# Mirrors_Controls.net
KiCad netlist of a schematic drawn in EAGLE
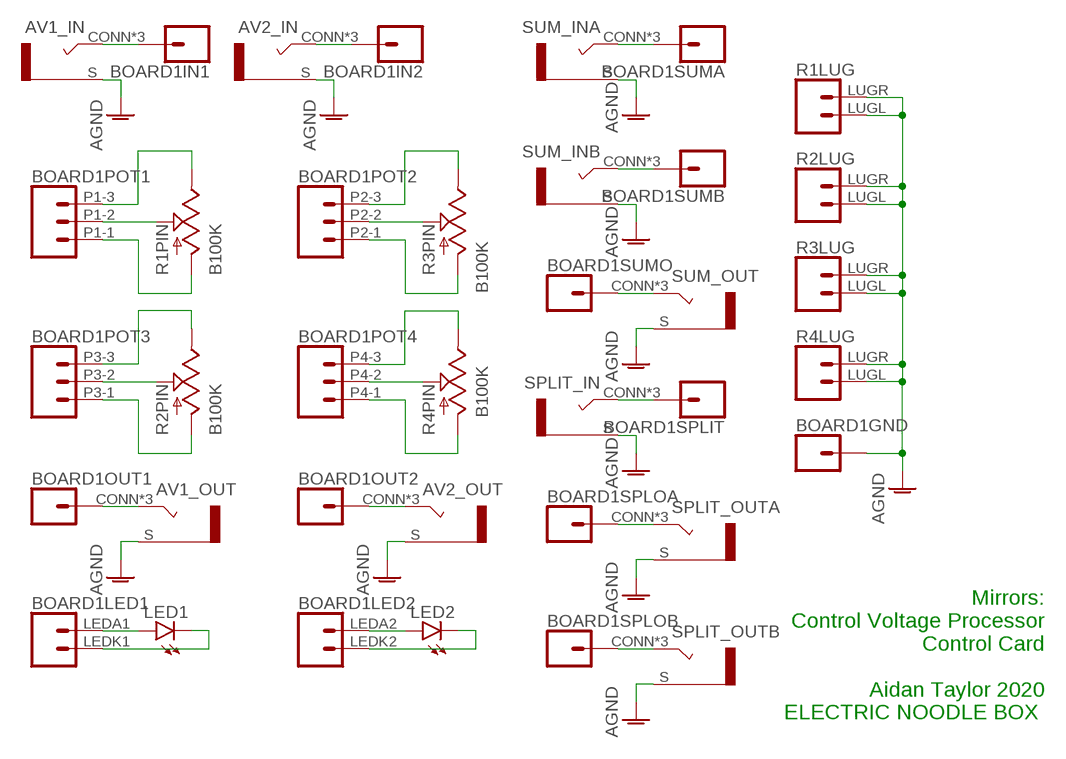
[diagram p0: schematic, sheet 1]

(export (version "E")
  (design (tool "Eeschema 10.0.6"))
  (components
    (comp (ref "AV1_IN")
      (value "COMBI-JACKCINCHNANA")
      (footprint "eagle-import:NEWCOMBOJACK_PANEL")
      (libsource (lib "eagle-import") (part "COMBI-JACKCINCHNANA"))
    )
    (comp (ref "AV1_OUT")
      (value "COMBI-JACKCINCHNANA")
      (footprint "eagle-import:NEWCOMBOJACK_PANEL")
      (libsource (lib "eagle-import") (part "COMBI-JACKCINCHNANA"))
    )
    (comp (ref "AV2_IN")
      (value "COMBI-JACKCINCHNANA")
      (footprint "eagle-import:NEWCOMBOJACK_PANEL")
      (libsource (lib "eagle-import") (part "COMBI-JACKCINCHNANA"))
    )
    (comp (ref "AV2_OUT")
      (value "COMBI-JACKCINCHNANA")
      (footprint "eagle-import:NEWCOMBOJACK_PANEL")
      (libsource (lib "eagle-import") (part "COMBI-JACKCINCHNANA"))
    )
    (comp (ref "BOARD1")
      (value "MIRRORS_LINK")
      (footprint "eagle-import:MIRRORS")
      (libsource (lib "eagle-import") (part "MIRRORS_LINK"))
    )
    (comp (ref "LED1")
      (value "LED5MM")
      (footprint "eagle-import:LED5MM")
      (libsource (lib "eagle-import") (part "LED5MM"))
    )
    (comp (ref "LED2")
      (value "LED5MM")
      (footprint "eagle-import:LED5MM")
      (libsource (lib "eagle-import") (part "LED5MM"))
    )
    (comp (ref "R1")
      (value "B100K")
      (footprint "eagle-import:ALPHA_RV09_9MMPOT")
      (libsource (lib "eagle-import") (part "POTENTIOMETER"))
    )
    (comp (ref "R2")
      (value "B100K")
      (footprint "eagle-import:ALPHA_RV09_9MMPOT")
      (libsource (lib "eagle-import") (part "POTENTIOMETER"))
    )
    (comp (ref "R3")
      (value "B100K")
      (footprint "eagle-import:ALPHA_RV09_9MMPOT")
      (libsource (lib "eagle-import") (part "POTENTIOMETER"))
    )
    (comp (ref "R4")
      (value "B100K")
      (footprint "eagle-import:ALPHA_RV09_9MMPOT")
      (libsource (lib "eagle-import") (part "POTENTIOMETER"))
    )
    (comp (ref "SPLIT_IN")
      (value "COMBI-JACKCINCHNANA")
      (footprint "eagle-import:NEWCOMBOJACK_PANEL")
      (libsource (lib "eagle-import") (part "COMBI-JACKCINCHNANA"))
    )
    (comp (ref "SPLIT_OUTA")
      (value "COMBI-JACKCINCHNANA")
      (footprint "eagle-import:NEWCOMBOJACK_PANEL")
      (libsource (lib "eagle-import") (part "COMBI-JACKCINCHNANA"))
    )
    (comp (ref "SPLIT_OUTB")
      (value "COMBI-JACKCINCHNANA")
      (footprint "eagle-import:NEWCOMBOJACK_PANEL")
      (libsource (lib "eagle-import") (part "COMBI-JACKCINCHNANA"))
    )
    (comp (ref "SUM_INA")
      (value "COMBI-JACKCINCHNANA")
      (footprint "eagle-import:NEWCOMBOJACK_PANEL")
      (libsource (lib "eagle-import") (part "COMBI-JACKCINCHNANA"))
    )
    (comp (ref "SUM_INB")
      (value "COMBI-JACKCINCHNANA")
      (footprint "eagle-import:NEWCOMBOJACK_PANEL")
      (libsource (lib "eagle-import") (part "COMBI-JACKCINCHNANA"))
    )
    (comp (ref "SUM_OUT")
      (value "COMBI-JACKCINCHNANA")
      (footprint "eagle-import:NEWCOMBOJACK_PANEL")
      (libsource (lib "eagle-import") (part "COMBI-JACKCINCHNANA"))
    )
  )
  (nets
    (net (code "1") (name "AGND") (class "Default")
      (node (ref "AV1_IN") (pin "S") (pinfunction "S_S") (pintype "passive"))
      (node (ref "AV1_OUT") (pin "S") (pinfunction "S_S") (pintype "passive"))
      (node (ref "AV2_IN") (pin "S") (pinfunction "S_S") (pintype "passive"))
      (node (ref "AV2_OUT") (pin "S") (pinfunction "S_S") (pintype "passive"))
      (node (ref "BOARD1") (pin "GND") (pinfunction "1_GND") (pintype "passive"))
      (node (ref "R1") (pin "LUGL") (pinfunction "1_LUGL") (pintype "passive"))
      (node (ref "R1") (pin "LUGR") (pinfunction "2_LUGR") (pintype "passive"))
      (node (ref "R2") (pin "LUGL") (pinfunction "1_LUGL") (pintype "passive"))
      (node (ref "R2") (pin "LUGR") (pinfunction "2_LUGR") (pintype "passive"))
      (node (ref "R3") (pin "LUGL") (pinfunction "1_LUGL") (pintype "passive"))
      (node (ref "R3") (pin "LUGR") (pinfunction "2_LUGR") (pintype "passive"))
      (node (ref "R4") (pin "LUGL") (pinfunction "1_LUGL") (pintype "passive"))
      (node (ref "R4") (pin "LUGR") (pinfunction "2_LUGR") (pintype "passive"))
      (node (ref "SPLIT_IN") (pin "S") (pinfunction "S_S") (pintype "passive"))
      (node (ref "SPLIT_OUTA") (pin "S") (pinfunction "S_S") (pintype "passive"))
      (node (ref "SPLIT_OUTB") (pin "S") (pinfunction "S_S") (pintype "passive"))
      (node (ref "SUM_INA") (pin "S") (pinfunction "S_S") (pintype "passive"))
      (node (ref "SUM_INB") (pin "S") (pinfunction "S_S") (pintype "passive"))
      (node (ref "SUM_OUT") (pin "S") (pinfunction "S_S") (pintype "passive"))
    )
    (net (code "2") (name "Net-(BOARD1B-1)") (class "Default")
      (node (ref "AV1_IN") (pin "CONN") (pinfunction "T_CONN") (pintype "passive"))
      (node (ref "AV1_IN") (pin "T1") (pinfunction "T_T1") (pintype "passive"))
      (node (ref "AV1_IN") (pin "T2") (pinfunction "T_T2") (pintype "passive"))
      (node (ref "BOARD1") (pin "IN1") (pinfunction "1_IN1") (pintype "passive"))
    )
    (net (code "3") (name "Net-(BOARD1C-1)") (class "Default")
      (node (ref "AV2_IN") (pin "CONN") (pinfunction "T_CONN") (pintype "passive"))
      (node (ref "AV2_IN") (pin "T1") (pinfunction "T_T1") (pintype "passive"))
      (node (ref "AV2_IN") (pin "T2") (pinfunction "T_T2") (pintype "passive"))
      (node (ref "BOARD1") (pin "IN2") (pinfunction "1_IN2") (pintype "passive"))
    )
    (net (code "4") (name "Net-(BOARD1D-1)") (class "Default")
      (node (ref "BOARD1") (pin "LEDK1") (pinfunction "1_LEDK1") (pintype "passive"))
      (node (ref "LED1") (pin "K") (pinfunction "C_K") (pintype "passive"))
    )
    (net (code "5") (name "Net-(BOARD1D-2)") (class "Default")
      (node (ref "BOARD1") (pin "LEDA1") (pinfunction "2_LEDA1") (pintype "passive"))
      (node (ref "LED1") (pin "A") (pinfunction "A_A") (pintype "passive"))
    )
    (net (code "6") (name "Net-(BOARD1E-1)") (class "Default")
      (node (ref "BOARD1") (pin "LEDK2") (pinfunction "1_LEDK2") (pintype "passive"))
      (node (ref "LED2") (pin "K") (pinfunction "C_K") (pintype "passive"))
    )
    (net (code "7") (name "Net-(BOARD1E-2)") (class "Default")
      (node (ref "BOARD1") (pin "LEDA2") (pinfunction "2_LEDA2") (pintype "passive"))
      (node (ref "LED2") (pin "A") (pinfunction "A_A") (pintype "passive"))
    )
    (net (code "8") (name "Net-(BOARD1F-1)") (class "Default")
      (node (ref "AV1_OUT") (pin "CONN") (pinfunction "T_CONN") (pintype "passive"))
      (node (ref "AV1_OUT") (pin "T1") (pinfunction "T_T1") (pintype "passive"))
      (node (ref "AV1_OUT") (pin "T2") (pinfunction "T_T2") (pintype "passive"))
      (node (ref "BOARD1") (pin "OUT1") (pinfunction "1_OUT1") (pintype "passive"))
    )
    (net (code "9") (name "Net-(BOARD1G-1)") (class "Default")
      (node (ref "AV2_OUT") (pin "CONN") (pinfunction "T_CONN") (pintype "passive"))
      (node (ref "AV2_OUT") (pin "T1") (pinfunction "T_T1") (pintype "passive"))
      (node (ref "AV2_OUT") (pin "T2") (pinfunction "T_T2") (pintype "passive"))
      (node (ref "BOARD1") (pin "OUT2") (pinfunction "1_OUT2") (pintype "passive"))
    )
    (net (code "10") (name "Net-(BOARD1H-1)") (class "Default")
      (node (ref "BOARD1") (pin "P1-1") (pinfunction "1_P1-1") (pintype "passive"))
      (node (ref "R1") (pin "C1") (pinfunction "A_C1") (pintype "passive"))
    )
    (net (code "11") (name "Net-(BOARD1H-2)") (class "Default")
      (node (ref "BOARD1") (pin "P1-2") (pinfunction "2_P1-2") (pintype "passive"))
      (node (ref "R1") (pin "C2") (pinfunction "W_C2") (pintype "passive"))
    )
    (net (code "12") (name "Net-(BOARD1H-3)") (class "Default")
      (node (ref "BOARD1") (pin "P1-3") (pinfunction "3_P1-3") (pintype "passive"))
      (node (ref "R1") (pin "C3") (pinfunction "B_C3") (pintype "passive"))
    )
    (net (code "13") (name "Net-(BOARD1I-1)") (class "Default")
      (node (ref "BOARD1") (pin "P2-1") (pinfunction "1_P2-1") (pintype "passive"))
      (node (ref "R3") (pin "C1") (pinfunction "A_C1") (pintype "passive"))
    )
    (net (code "14") (name "Net-(BOARD1I-2)") (class "Default")
      (node (ref "BOARD1") (pin "P2-2") (pinfunction "2_P2-2") (pintype "passive"))
      (node (ref "R3") (pin "C2") (pinfunction "W_C2") (pintype "passive"))
    )
    (net (code "15") (name "Net-(BOARD1I-3)") (class "Default")
      (node (ref "BOARD1") (pin "P2-3") (pinfunction "3_P2-3") (pintype "passive"))
      (node (ref "R3") (pin "C3") (pinfunction "B_C3") (pintype "passive"))
    )
    (net (code "16") (name "Net-(BOARD1J-1)") (class "Default")
      (node (ref "BOARD1") (pin "P3-1") (pinfunction "1_P3-1") (pintype "passive"))
      (node (ref "R2") (pin "C1") (pinfunction "A_C1") (pintype "passive"))
    )
    (net (code "17") (name "Net-(BOARD1J-2)") (class "Default")
      (node (ref "BOARD1") (pin "P3-2") (pinfunction "2_P3-2") (pintype "passive"))
      (node (ref "R2") (pin "C2") (pinfunction "W_C2") (pintype "passive"))
    )
    (net (code "18") (name "Net-(BOARD1J-3)") (class "Default")
      (node (ref "BOARD1") (pin "P3-3") (pinfunction "3_P3-3") (pintype "passive"))
      (node (ref "R2") (pin "C3") (pinfunction "B_C3") (pintype "passive"))
    )
    (net (code "19") (name "Net-(BOARD1K-1)") (class "Default")
      (node (ref "BOARD1") (pin "P4-1") (pinfunction "1_P4-1") (pintype "passive"))
      (node (ref "R4") (pin "C1") (pinfunction "A_C1") (pintype "passive"))
    )
    (net (code "20") (name "Net-(BOARD1K-2)") (class "Default")
      (node (ref "BOARD1") (pin "P4-2") (pinfunction "2_P4-2") (pintype "passive"))
      (node (ref "R4") (pin "C2") (pinfunction "W_C2") (pintype "passive"))
    )
    (net (code "21") (name "Net-(BOARD1K-3)") (class "Default")
      (node (ref "BOARD1") (pin "P4-3") (pinfunction "3_P4-3") (pintype "passive"))
      (node (ref "R4") (pin "C3") (pinfunction "B_C3") (pintype "passive"))
    )
    (net (code "22") (name "Net-(BOARD1L-1)") (class "Default")
      (node (ref "BOARD1") (pin "SPLIT") (pinfunction "1_SPLIT") (pintype "passive"))
      (node (ref "SPLIT_IN") (pin "CONN") (pinfunction "T_CONN") (pintype "passive"))
      (node (ref "SPLIT_IN") (pin "T1") (pinfunction "T_T1") (pintype "passive"))
      (node (ref "SPLIT_IN") (pin "T2") (pinfunction "T_T2") (pintype "passive"))
    )
    (net (code "23") (name "Net-(BOARD1M-1)") (class "Default")
      (node (ref "BOARD1") (pin "SPLOA") (pinfunction "1_SPLOA") (pintype "passive"))
      (node (ref "SPLIT_OUTA") (pin "CONN") (pinfunction "T_CONN") (pintype "passive"))
      (node (ref "SPLIT_OUTA") (pin "T1") (pinfunction "T_T1") (pintype "passive"))
      (node (ref "SPLIT_OUTA") (pin "T2") (pinfunction "T_T2") (pintype "passive"))
    )
    (net (code "24") (name "Net-(BOARD1N-1)") (class "Default")
      (node (ref "BOARD1") (pin "SPLOB") (pinfunction "1_SPLOB") (pintype "passive"))
      (node (ref "SPLIT_OUTB") (pin "CONN") (pinfunction "T_CONN") (pintype "passive"))
      (node (ref "SPLIT_OUTB") (pin "T1") (pinfunction "T_T1") (pintype "passive"))
      (node (ref "SPLIT_OUTB") (pin "T2") (pinfunction "T_T2") (pintype "passive"))
    )
    (net (code "25") (name "Net-(BOARD1O-1)") (class "Default")
      (node (ref "BOARD1") (pin "SUMA") (pinfunction "1_SUMA") (pintype "passive"))
      (node (ref "SUM_INA") (pin "CONN") (pinfunction "T_CONN") (pintype "passive"))
      (node (ref "SUM_INA") (pin "T1") (pinfunction "T_T1") (pintype "passive"))
      (node (ref "SUM_INA") (pin "T2") (pinfunction "T_T2") (pintype "passive"))
    )
    (net (code "26") (name "Net-(BOARD1P-1)") (class "Default")
      (node (ref "BOARD1") (pin "SUMB") (pinfunction "1_SUMB") (pintype "passive"))
      (node (ref "SUM_INB") (pin "CONN") (pinfunction "T_CONN") (pintype "passive"))
      (node (ref "SUM_INB") (pin "T1") (pinfunction "T_T1") (pintype "passive"))
      (node (ref "SUM_INB") (pin "T2") (pinfunction "T_T2") (pintype "passive"))
    )
    (net (code "27") (name "Net-(BOARD1Q-1)") (class "Default")
      (node (ref "BOARD1") (pin "SUMO") (pinfunction "1_SUMO") (pintype "passive"))
      (node (ref "SUM_OUT") (pin "CONN") (pinfunction "T_CONN") (pintype "passive"))
      (node (ref "SUM_OUT") (pin "T1") (pinfunction "T_T1") (pintype "passive"))
      (node (ref "SUM_OUT") (pin "T2") (pinfunction "T_T2") (pintype "passive"))
    )
  )
)
